# design.net
KiCad netlist of a schematic drawn in Altium Designer
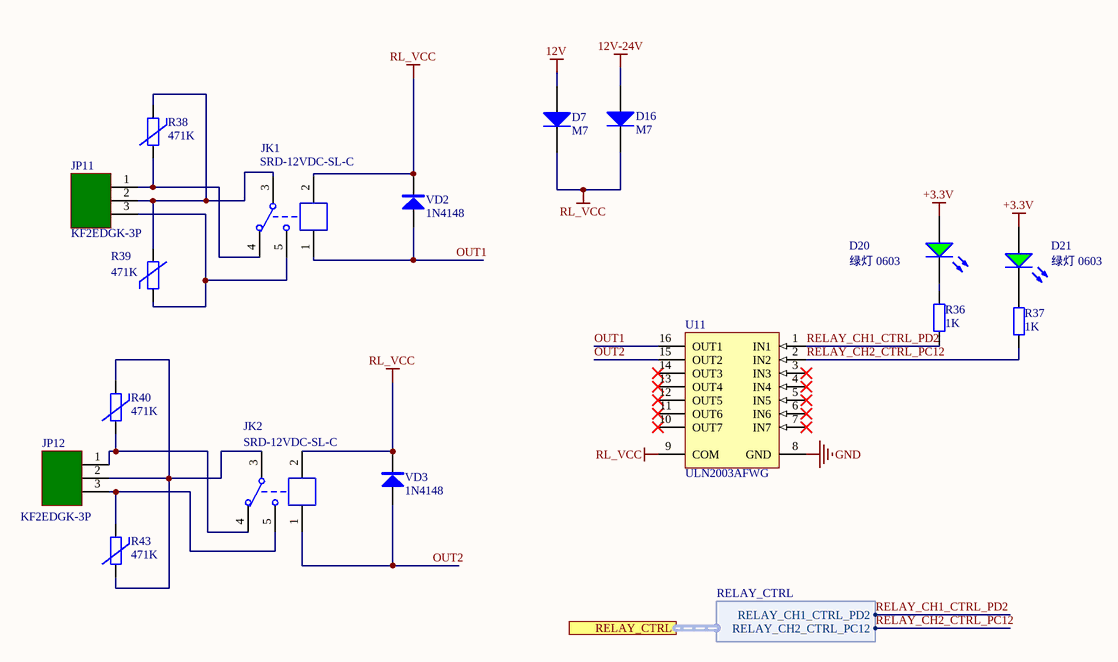
[diagram p0: 继电器.SchDoc]

(export (version "E")
  (design (tool "Eeschema 10.0.6"))
  (components
    (comp (ref "D7")
      (value "M7")
      (footprint "SMA(DO-214AC)_S1")
      (description "二极管")
      (libsource (lib "Miscellaneous Devices LC") (part "SMA(DO-214AC) M7"))
    )
    (comp (ref "D16")
      (value "M7")
      (footprint "SMA(DO-214AC)_S1")
      (description "二极管")
      (libsource (lib "Miscellaneous Devices LC") (part "SMA(DO-214AC) M7"))
    )
    (comp (ref "D20")
      (value "绿灯 0603")
      (footprint "0603_LED_S1")
      (description "发光二极管")
      (libsource (lib "Miscellaneous Devices LC") (part "0603 绿灯"))
    )
    (comp (ref "D21")
      (value "绿灯 0603")
      (footprint "0603_LED_S1")
      (description "发光二极管")
      (libsource (lib "Miscellaneous Devices LC") (part "0603 绿灯"))
    )
    (comp (ref "JK1")
      (value "SRD-12VDC-SL-C")
      (footprint "SRD-C_B")
      (description "12V单路双控继电器")
      (fields (field (name "版权归属") "源创客"))
      (libsource (lib "源创客") (part "SRD-12VDC-SL-C"))
    )
    (comp (ref "JK2")
      (value "SRD-12VDC-SL-C")
      (footprint "SRD-C_B")
      (description "12V单路双控继电器")
      (fields (field (name "版权归属") "源创客"))
      (libsource (lib "源创客") (part "SRD-12VDC-SL-C"))
    )
    (comp (ref "JP11")
      (value "KF2EDGK-3P")
      (footprint "KF2EDGK5.08W-3P")
      (libsource (lib "KF2EDGK") (part "KF2EDGK-3P"))
    )
    (comp (ref "JP12")
      (value "KF2EDGK-3P")
      (footprint "KF2EDGK5.08W-3P")
      (libsource (lib "KF2EDGK") (part "KF2EDGK-3P"))
    )
    (comp (ref "R36")
      (value "1K")
      (footprint "0603_R")
      (description "贴片电阻")
      (libsource (lib "Miscellaneous Devices LC") (part "0603 510Ω (5100) 1%"))
    )
    (comp (ref "R37")
      (value "1K")
      (footprint "0603_R")
      (description "贴片电阻")
      (libsource (lib "Miscellaneous Devices LC") (part "0603 510Ω (5100) 1%"))
    )
    (comp (ref "R38")
      (value "471K")
      (footprint "VDR 9D-4.5")
      (description "压敏电阻")
      (fields (field (name "版权归属") "源创客"))
      (libsource (lib "源创客") (part "R_VDR"))
    )
    (comp (ref "R39")
      (value "471K")
      (footprint "VDR 9D-4.5")
      (description "压敏电阻")
      (fields (field (name "版权归属") "源创客"))
      (libsource (lib "源创客") (part "R_VDR"))
    )
    (comp (ref "R40")
      (value "471K")
      (footprint "VDR 9D-4.5")
      (description "压敏电阻")
      (fields (field (name "版权归属") "源创客"))
      (libsource (lib "源创客") (part "R_VDR"))
    )
    (comp (ref "R43")
      (value "471K")
      (footprint "VDR 9D-4.5")
      (description "压敏电阻")
      (fields (field (name "版权归属") "源创客"))
      (libsource (lib "源创客") (part "R_VDR"))
    )
    (comp (ref "U11")
      (value "ULN2003AFWG")
      (footprint "SOIC-16_150mil")
      (description "大电流驱动")
      (libsource (lib "Miscellaneous Devices LC") (part "ULN2003AFWG"))
    )
    (comp (ref "VD2")
      (value "1N4148")
      (footprint "MINI_MELF (LL34)")
      (description "高速开关二极管")
      (fields (field (name "版权归属") "源创客"))
      (libsource (lib "源创客") (part "1N4148"))
    )
    (comp (ref "VD3")
      (value "1N4148")
      (footprint "MINI_MELF (LL34)")
      (description "高速开关二极管")
      (fields (field (name "版权归属") "源创客"))
      (libsource (lib "源创客") (part "1N4148"))
    )
  )
  (nets
    (net (code "2") (name "+3.3V") (class "Default")
      (node (ref "D20") (pin "A") (pinfunction "A_A") (pintype "passive"))
      (node (ref "D21") (pin "A") (pinfunction "A_A") (pintype "passive"))
    )
    (net (code "3") (name "/OUT1") (class "Default")
      (node (ref "JK1") (pin "1") (pinfunction "1_1") (pintype "passive"))
      (node (ref "U11") (pin "16") (pinfunction "OUT1_16") (pintype "open_collector"))
      (node (ref "VD2") (pin "1") (pinfunction "A_1") (pintype "passive"))
    )
    (net (code "4") (name "/OUT2") (class "Default")
      (node (ref "JK2") (pin "1") (pinfunction "1_1") (pintype "passive"))
      (node (ref "U11") (pin "15") (pinfunction "OUT2_15") (pintype "open_collector"))
      (node (ref "VD3") (pin "1") (pinfunction "A_1") (pintype "passive"))
    )
    (net (code "5") (name "/RELAY_CH1_CTRL_PD2") (class "Default")
      (node (ref "R36") (pin "1") (pinfunction "1_1") (pintype "passive"))
      (node (ref "U11") (pin "1") (pinfunction "IN1_1") (pintype "input"))
    )
    (net (code "6") (name "/RELAY_CH2_CTRL_PC12") (class "Default")
      (node (ref "R37") (pin "1") (pinfunction "1_1") (pintype "passive"))
      (node (ref "U11") (pin "2") (pinfunction "IN2_2") (pintype "input"))
    )
    (net (code "8") (name "12V") (class "Default")
      (node (ref "D7") (pin "1") (pinfunction "A_1") (pintype "passive"))
    )
    (net (code "9") (name "12V-24V") (class "Default")
      (node (ref "D16") (pin "1") (pinfunction "A_1") (pintype "passive"))
    )
    (net (code "10") (name "GND") (class "Default")
      (node (ref "U11") (pin "8") (pinfunction "GND_8") (pintype "power_in"))
    )
    (net (code "11") (name "Net-(D20-PadK)") (class "Default")
      (node (ref "D20") (pin "K") (pinfunction "K_K") (pintype "passive"))
      (node (ref "R36") (pin "2") (pinfunction "2_2") (pintype "passive"))
    )
    (net (code "12") (name "Net-(D21-PadK)") (class "Default")
      (node (ref "D21") (pin "K") (pinfunction "K_K") (pintype "passive"))
      (node (ref "R37") (pin "2") (pinfunction "2_2") (pintype "passive"))
    )
    (net (code "13") (name "Net-(JK1-Pad3)") (class "Default")
      (node (ref "JK1") (pin "3") (pinfunction "3_3") (pintype "passive"))
      (node (ref "JP11") (pin "2") (pinfunction "2_2") (pintype "passive"))
      (node (ref "R38") (pin "1") (pinfunction "1_1") (pintype "passive"))
      (node (ref "R39") (pin "2") (pinfunction "2_2") (pintype "passive"))
    )
    (net (code "14") (name "Net-(JK1-Pad4)") (class "Default")
      (node (ref "JK1") (pin "4") (pinfunction "4_4") (pintype "passive"))
      (node (ref "JP11") (pin "1") (pinfunction "1_1") (pintype "passive"))
      (node (ref "R38") (pin "2") (pinfunction "2_2") (pintype "passive"))
    )
    (net (code "15") (name "Net-(JK1-Pad5)") (class "Default")
      (node (ref "JK1") (pin "5") (pinfunction "5_5") (pintype "passive"))
      (node (ref "JP11") (pin "3") (pinfunction "3_3") (pintype "passive"))
      (node (ref "R39") (pin "1") (pinfunction "1_1") (pintype "passive"))
    )
    (net (code "16") (name "Net-(JK2-Pad3)") (class "Default")
      (node (ref "JK2") (pin "3") (pinfunction "3_3") (pintype "passive"))
      (node (ref "JP12") (pin "2") (pinfunction "2_2") (pintype "passive"))
      (node (ref "R40") (pin "1") (pinfunction "1_1") (pintype "passive"))
      (node (ref "R43") (pin "2") (pinfunction "2_2") (pintype "passive"))
    )
    (net (code "17") (name "Net-(JK2-Pad4)") (class "Default")
      (node (ref "JK2") (pin "4") (pinfunction "4_4") (pintype "passive"))
      (node (ref "JP12") (pin "1") (pinfunction "1_1") (pintype "passive"))
      (node (ref "R40") (pin "2") (pinfunction "2_2") (pintype "passive"))
    )
    (net (code "18") (name "Net-(JK2-Pad5)") (class "Default")
      (node (ref "JK2") (pin "5") (pinfunction "5_5") (pintype "passive"))
      (node (ref "JP12") (pin "3") (pinfunction "3_3") (pintype "passive"))
      (node (ref "R43") (pin "1") (pinfunction "1_1") (pintype "passive"))
    )
    (net (code "19") (name "RL_VCC") (class "Default")
      (node (ref "D16") (pin "2") (pinfunction "K_2") (pintype "passive"))
      (node (ref "D7") (pin "2") (pinfunction "K_2") (pintype "passive"))
      (node (ref "JK1") (pin "2") (pinfunction "2_2") (pintype "passive"))
      (node (ref "JK2") (pin "2") (pinfunction "2_2") (pintype "passive"))
      (node (ref "U11") (pin "9") (pinfunction "COM_9") (pintype "passive"))
      (node (ref "VD2") (pin "2") (pinfunction "K_2") (pintype "passive"))
      (node (ref "VD3") (pin "2") (pinfunction "K_2") (pintype "passive"))
    )
    (net (code "20") (name "unconnected-(U11-IN3-Pad3)") (class "Default")
      (node (ref "U11") (pin "3") (pinfunction "IN3_3") (pintype "input+no_connect"))
    )
    (net (code "21") (name "unconnected-(U11-IN4-Pad4)") (class "Default")
      (node (ref "U11") (pin "4") (pinfunction "IN4_4") (pintype "input+no_connect"))
    )
    (net (code "22") (name "unconnected-(U11-IN5-Pad5)") (class "Default")
      (node (ref "U11") (pin "5") (pinfunction "IN5_5") (pintype "input+no_connect"))
    )
    (net (code "23") (name "unconnected-(U11-IN6-Pad6)") (class "Default")
      (node (ref "U11") (pin "6") (pinfunction "IN6_6") (pintype "input+no_connect"))
    )
    (net (code "24") (name "unconnected-(U11-IN7-Pad7)") (class "Default")
      (node (ref "U11") (pin "7") (pinfunction "IN7_7") (pintype "input+no_connect"))
    )
    (net (code "25") (name "unconnected-(U11-OUT3-Pad14)") (class "Default")
      (node (ref "U11") (pin "14") (pinfunction "OUT3_14") (pintype "open_collector+no_connect"))
    )
    (net (code "26") (name "unconnected-(U11-OUT4-Pad13)") (class "Default")
      (node (ref "U11") (pin "13") (pinfunction "OUT4_13") (pintype "open_collector+no_connect"))
    )
    (net (code "27") (name "unconnected-(U11-OUT5-Pad12)") (class "Default")
      (node (ref "U11") (pin "12") (pinfunction "OUT5_12") (pintype "open_collector+no_connect"))
    )
    (net (code "28") (name "unconnected-(U11-OUT6-Pad11)") (class "Default")
      (node (ref "U11") (pin "11") (pinfunction "OUT6_11") (pintype "open_collector+no_connect"))
    )
    (net (code "29") (name "unconnected-(U11-OUT7-Pad10)") (class "Default")
      (node (ref "U11") (pin "10") (pinfunction "OUT7_10") (pintype "open_collector+no_connect"))
    )
  )
)
